# SCH_Flight-Computer-V4_2024-07-29.net
KiCad netlist of a schematic drawn in EasyEDA
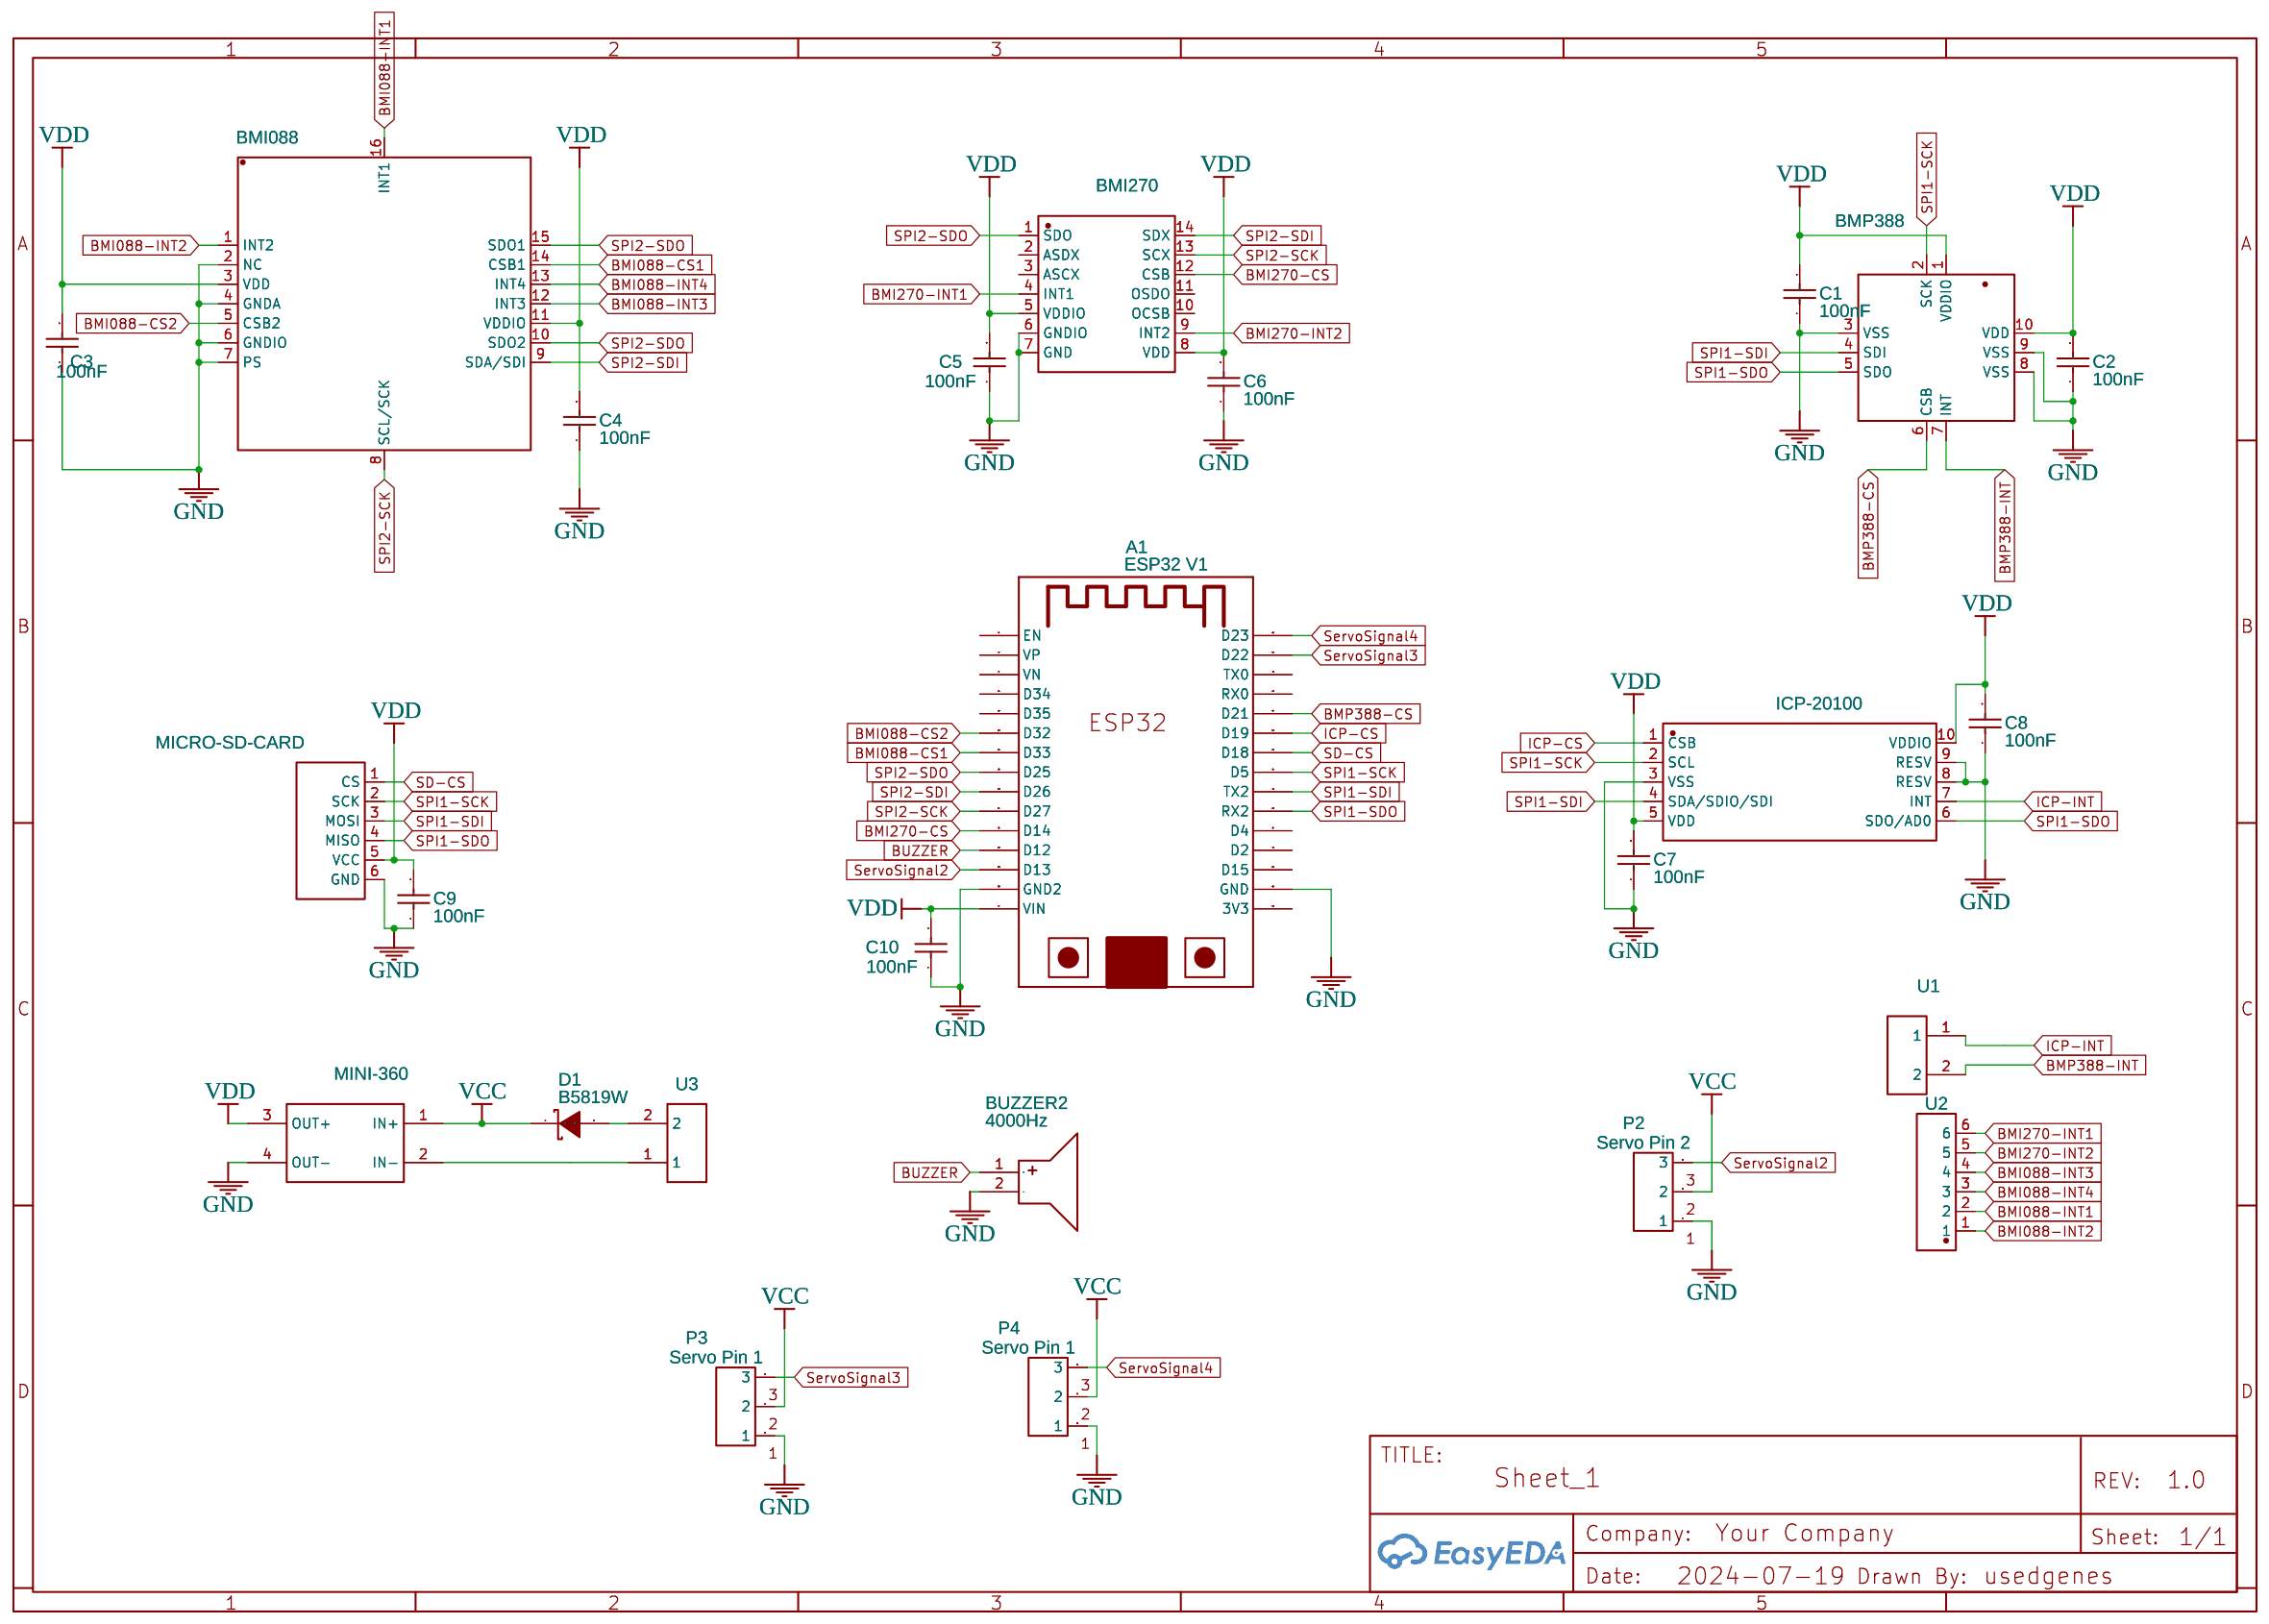
[diagram p0: schematic sheet]

(export (version "E")
  (design (tool "Eeschema 10.0.6"))
  (components
    (comp (ref "A1") (value "ESP32 V1") (libsource (lib "") (part "ESP32-DEVKIT-V1-30PIN")))
    (comp (ref "BMI088")
      (value "BMI088")
      (fields (field (name "Manufacturer") "Bosch(博世)"))
      (libsource (lib "") (part "BMI088"))
    )
    (comp (ref "BMI270")
      (value "BMI270")
      (fields (field (name "Manufacturer") "Bosch(博世)"))
      (libsource (lib "") (part "BMI270"))
    )
    (comp (ref "BMP388")
      (value "BMP388")
      (fields (field (name "Manufacturer") "Bosch(博世)"))
      (libsource (lib "") (part "BMP388"))
    )
    (comp (ref "BUZZER2")
      (value "4000Hz")
      (fields
        (field (name "Manufacturer Part") "SKY-1475-0540-45P7.6")
        (field (name "Manufacturer") "S&S(海旭)")
      )
      (libsource (lib "") (part "SKY-1475-0540-45P7.6"))
    )
    (comp (ref "C1")
      (value "100nF")
      (fields
        (field (name "Manufacturer Part") "CL05B104KO5NNNC")
        (field (name "Manufacturer") "SAMSUNG(三星)")
      )
      (libsource (lib "") (part "CL05B104KO5NNNC"))
    )
    (comp (ref "C2")
      (value "100nF")
      (fields
        (field (name "Manufacturer Part") "CL05B104KO5NNNC")
        (field (name "Manufacturer") "SAMSUNG(三星)")
      )
      (libsource (lib "") (part "CL05B104KO5NNNC"))
    )
    (comp (ref "C3")
      (value "100nF")
      (fields
        (field (name "Manufacturer Part") "CL05B104KO5NNNC")
        (field (name "Manufacturer") "SAMSUNG(三星)")
      )
      (libsource (lib "") (part "CL05B104KO5NNNC"))
    )
    (comp (ref "C4")
      (value "100nF")
      (fields
        (field (name "Manufacturer Part") "CL05B104KO5NNNC")
        (field (name "Manufacturer") "SAMSUNG(三星)")
      )
      (libsource (lib "") (part "CL05B104KO5NNNC"))
    )
    (comp (ref "C5")
      (value "100nF")
      (fields
        (field (name "Manufacturer Part") "CL05B104KO5NNNC")
        (field (name "Manufacturer") "SAMSUNG(三星)")
      )
      (libsource (lib "") (part "CL05B104KO5NNNC"))
    )
    (comp (ref "C6")
      (value "100nF")
      (fields
        (field (name "Manufacturer Part") "CL05B104KO5NNNC")
        (field (name "Manufacturer") "SAMSUNG(三星)")
      )
      (libsource (lib "") (part "CL05B104KO5NNNC"))
    )
    (comp (ref "C7")
      (value "100nF")
      (fields
        (field (name "Manufacturer Part") "CL05B104KO5NNNC")
        (field (name "Manufacturer") "SAMSUNG(三星)")
      )
      (libsource (lib "") (part "CL05B104KO5NNNC"))
    )
    (comp (ref "C8")
      (value "100nF")
      (fields
        (field (name "Manufacturer Part") "CL05B104KO5NNNC")
        (field (name "Manufacturer") "SAMSUNG(三星)")
      )
      (libsource (lib "") (part "CL05B104KO5NNNC"))
    )
    (comp (ref "C9")
      (value "100nF")
      (fields
        (field (name "Manufacturer Part") "CL05B104KO5NNNC")
        (field (name "Manufacturer") "SAMSUNG(三星)")
      )
      (libsource (lib "") (part "CL05B104KO5NNNC"))
    )
    (comp (ref "C10")
      (value "100nF")
      (fields
        (field (name "Manufacturer Part") "CL05B104KO5NNNC")
        (field (name "Manufacturer") "SAMSUNG(三星)")
      )
      (libsource (lib "") (part "CL05B104KO5NNNC"))
    )
    (comp (ref "D1")
      (value "B5819W")
      (fields (field (name "Manufacturer") "MDD(辰达半导体)"))
      (libsource (lib "") (part "B5819W"))
    )
    (comp (ref "ICP-20100")
      (value "ICP-20100")
      (fields (field (name "Manufacturer") "TDK"))
      (libsource (lib "") (part "ICP-20100"))
    )
    (comp (ref "MICRO-SD-CARD") (value "MicroSDCardAdapter") (libsource (lib "") (part "MicroSDCardAdapter")))
    (comp (ref "MINI-360") (value "MINI-360") (libsource (lib "") (part "MINI-360")))
    (comp (ref "P2")
      (value "Servo Pin 2")
      (fields
        (field (name "Manufacturer Part") "Female headerHDR1X8-2.54")
        (field (name "Manufacturer") "BOOMELE")
      )
      (libsource (lib "") (part "HEADER PAD 3X RMM COPY"))
    )
    (comp (ref "P3")
      (value "Servo Pin 1")
      (fields
        (field (name "Manufacturer Part") "Female headerHDR1X8-2.54")
        (field (name "Manufacturer") "BOOMELE")
      )
      (libsource (lib "") (part "HEADER PAD 3X RMM COPY"))
    )
    (comp (ref "P4")
      (value "Servo Pin 1")
      (fields
        (field (name "Manufacturer Part") "Female headerHDR1X8-2.54")
        (field (name "Manufacturer") "BOOMELE")
      )
      (libsource (lib "") (part "HEADER PAD 3X RMM COPY"))
    )
    (comp (ref "U1") (value "Power Pins") (libsource (lib "") (part "1X2_1")))
    (comp (ref "U2")
      (value "PIN HEADER 1X6PIN 2.54MM 6P OK COPY")
      (libsource (lib "") (part "PIN HEADER 1X6PIN 2.54MM 6P OK COPY"))
    )
    (comp (ref "U3") (value "Power Pins") (libsource (lib "") (part "1X2")))
  )
  (nets
    (net (code "1") (name "BMI088-CS1") (class "Default")
      (node (ref "A1") (pin "D33") (pinfunction "D33_D33") (pintype "unspecified"))
      (node (ref "BMI088") (pin "14") (pinfunction "CSB1_14") (pintype "unspecified"))
    )
    (net (code "2") (name "BMI088-CS2") (class "Default")
      (node (ref "A1") (pin "D32") (pinfunction "D32_D32") (pintype "unspecified"))
      (node (ref "BMI088") (pin "5") (pinfunction "CSB2_5") (pintype "unspecified"))
    )
    (net (code "3") (name "BMI088-INT1") (class "Default")
      (node (ref "BMI088") (pin "16") (pinfunction "INT1_16") (pintype "unspecified"))
      (node (ref "U2") (pin "2") (pinfunction "2_2") (pintype "unspecified"))
    )
    (net (code "4") (name "BMI088-INT2") (class "Default")
      (node (ref "BMI088") (pin "1") (pinfunction "INT2_1") (pintype "unspecified"))
      (node (ref "U2") (pin "1") (pinfunction "1_1") (pintype "unspecified"))
    )
    (net (code "5") (name "BMI088-INT3") (class "Default")
      (node (ref "BMI088") (pin "12") (pinfunction "INT3_12") (pintype "unspecified"))
      (node (ref "U2") (pin "4") (pinfunction "4_4") (pintype "unspecified"))
    )
    (net (code "6") (name "BMI088-INT4") (class "Default")
      (node (ref "BMI088") (pin "13") (pinfunction "INT4_13") (pintype "unspecified"))
      (node (ref "U2") (pin "3") (pinfunction "3_3") (pintype "unspecified"))
    )
    (net (code "7") (name "BMI270-CS") (class "Default")
      (node (ref "A1") (pin "D14") (pinfunction "D14_D14") (pintype "unspecified"))
      (node (ref "BMI270") (pin "12") (pinfunction "CSB_12") (pintype "unspecified"))
    )
    (net (code "8") (name "BMI270-INT1") (class "Default")
      (node (ref "BMI270") (pin "4") (pinfunction "INT1_4") (pintype "unspecified"))
      (node (ref "U2") (pin "6") (pinfunction "6_6") (pintype "unspecified"))
    )
    (net (code "9") (name "BMI270-INT2") (class "Default")
      (node (ref "BMI270") (pin "9") (pinfunction "INT2_9") (pintype "unspecified"))
      (node (ref "U2") (pin "5") (pinfunction "5_5") (pintype "unspecified"))
    )
    (net (code "10") (name "BMP388-CS") (class "Default")
      (node (ref "A1") (pin "D21") (pinfunction "D21_D21") (pintype "unspecified"))
      (node (ref "BMP388") (pin "6") (pinfunction "CSB_6") (pintype "unspecified"))
    )
    (net (code "11") (name "BMP388-INT") (class "Default")
      (node (ref "BMP388") (pin "7") (pinfunction "INT_7") (pintype "unspecified"))
      (node (ref "U1") (pin "2") (pinfunction "2_2") (pintype "unspecified"))
    )
    (net (code "12") (name "BUZZER") (class "Default")
      (node (ref "A1") (pin "D12") (pinfunction "D12_D12") (pintype "unspecified"))
      (node (ref "BUZZER2") (pin "1") (pinfunction "+_1") (pintype "unspecified"))
    )
    (net (code "13") (name "GND") (class "Default")
      (node (ref "A1") (pin "GND") (pinfunction "GND_GND") (pintype "unspecified"))
      (node (ref "A1") (pin "GND2") (pinfunction "GND2_GND2") (pintype "unspecified"))
      (node (ref "BMI088") (pin "2") (pinfunction "NC_2") (pintype "unspecified"))
      (node (ref "BMI088") (pin "4") (pinfunction "GNDA_4") (pintype "unspecified"))
      (node (ref "BMI088") (pin "6") (pinfunction "GNDIO_6") (pintype "unspecified"))
      (node (ref "BMI088") (pin "7") (pinfunction "PS_7") (pintype "unspecified"))
      (node (ref "BMI270") (pin "6") (pinfunction "GNDIO_6") (pintype "unspecified"))
      (node (ref "BMI270") (pin "7") (pinfunction "GND_7") (pintype "unspecified"))
      (node (ref "BMP388") (pin "3") (pinfunction "VSS_3") (pintype "unspecified"))
      (node (ref "BMP388") (pin "8") (pinfunction "VSS_8") (pintype "unspecified"))
      (node (ref "BMP388") (pin "9") (pinfunction "VSS_9") (pintype "unspecified"))
      (node (ref "BUZZER2") (pin "2") (pinfunction "-_2") (pintype "unspecified"))
      (node (ref "C1") (pin "1") (pinfunction "1_1") (pintype "input"))
      (node (ref "C10") (pin "1") (pinfunction "1_1") (pintype "input"))
      (node (ref "C2") (pin "1") (pinfunction "1_1") (pintype "input"))
      (node (ref "C3") (pin "1") (pinfunction "1_1") (pintype "input"))
      (node (ref "C4") (pin "1") (pinfunction "1_1") (pintype "input"))
      (node (ref "C5") (pin "1") (pinfunction "1_1") (pintype "input"))
      (node (ref "C6") (pin "1") (pinfunction "1_1") (pintype "input"))
      (node (ref "C7") (pin "1") (pinfunction "1_1") (pintype "input"))
      (node (ref "C8") (pin "1") (pinfunction "1_1") (pintype "input"))
      (node (ref "C9") (pin "1") (pinfunction "1_1") (pintype "input"))
      (node (ref "ICP-20100") (pin "3") (pinfunction "VSS_3") (pintype "unspecified"))
      (node (ref "ICP-20100") (pin "8") (pinfunction "RESV_8") (pintype "unspecified"))
      (node (ref "ICP-20100") (pin "9") (pinfunction "RESV_9") (pintype "unspecified"))
      (node (ref "MICRO-SD-CARD") (pin "6") (pinfunction "GND_6") (pintype "passive"))
      (node (ref "MINI-360") (pin "4") (pinfunction "OUT-_4") (pintype "unspecified"))
      (node (ref "P2") (pin "1") (pinfunction "1_1") (pintype "unspecified"))
      (node (ref "P3") (pin "1") (pinfunction "1_1") (pintype "unspecified"))
      (node (ref "P4") (pin "1") (pinfunction "1_1") (pintype "unspecified"))
    )
    (net (code "14") (name "ICP-CS") (class "Default")
      (node (ref "A1") (pin "D19") (pinfunction "D19_D19") (pintype "unspecified"))
      (node (ref "ICP-20100") (pin "1") (pinfunction "CSB_1") (pintype "unspecified"))
    )
    (net (code "15") (name "ICP-INT") (class "Default")
      (node (ref "ICP-20100") (pin "7") (pinfunction "INT_7") (pintype "unspecified"))
      (node (ref "U1") (pin "1") (pinfunction "1_1") (pintype "unspecified"))
    )
    (net (code "16") (name "Net-(D1-A)") (class "Default")
      (node (ref "D1") (pin "2") (pinfunction "A_2") (pintype "unspecified"))
      (node (ref "U3") (pin "2") (pinfunction "2_2") (pintype "unspecified"))
    )
    (net (code "17") (name "Net-(MINI-360-IN-)") (class "Default")
      (node (ref "MINI-360") (pin "2") (pinfunction "IN-_2") (pintype "unspecified"))
      (node (ref "U3") (pin "1") (pinfunction "1_1") (pintype "unspecified"))
    )
    (net (code "18") (name "SD-CS") (class "Default")
      (node (ref "A1") (pin "D18") (pinfunction "D18_D18") (pintype "unspecified"))
      (node (ref "MICRO-SD-CARD") (pin "1") (pinfunction "CS_1") (pintype "bidirectional"))
    )
    (net (code "19") (name "SPI1-SCK") (class "Default")
      (node (ref "A1") (pin "D5") (pinfunction "D5_D5") (pintype "unspecified"))
      (node (ref "BMP388") (pin "2") (pinfunction "SCK_2") (pintype "unspecified"))
      (node (ref "ICP-20100") (pin "2") (pinfunction "SCL_2") (pintype "unspecified"))
      (node (ref "MICRO-SD-CARD") (pin "2") (pinfunction "SCK_2") (pintype "bidirectional"))
    )
    (net (code "20") (name "SPI1-SDI") (class "Default")
      (node (ref "A1") (pin "TX2") (pinfunction "TX2_TX2") (pintype "unspecified"))
      (node (ref "BMP388") (pin "4") (pinfunction "SDI_4") (pintype "unspecified"))
      (node (ref "ICP-20100") (pin "4") (pinfunction "SDA/SDIO/SDI_4") (pintype "unspecified"))
      (node (ref "MICRO-SD-CARD") (pin "3") (pinfunction "MOSI_3") (pintype "passive"))
    )
    (net (code "21") (name "SPI1-SDO") (class "Default")
      (node (ref "A1") (pin "RX2") (pinfunction "RX2_RX2") (pintype "unspecified"))
      (node (ref "BMP388") (pin "5") (pinfunction "SDO_5") (pintype "unspecified"))
      (node (ref "ICP-20100") (pin "6") (pinfunction "SDO/AD0_6") (pintype "unspecified"))
      (node (ref "MICRO-SD-CARD") (pin "4") (pinfunction "MISO_4") (pintype "bidirectional"))
    )
    (net (code "22") (name "SPI2-SCK") (class "Default")
      (node (ref "A1") (pin "D27") (pinfunction "D27_D27") (pintype "unspecified"))
      (node (ref "BMI088") (pin "8") (pinfunction "SCL/SCK_8") (pintype "unspecified"))
      (node (ref "BMI270") (pin "13") (pinfunction "SCX_13") (pintype "unspecified"))
    )
    (net (code "23") (name "SPI2-SDI") (class "Default")
      (node (ref "A1") (pin "D26") (pinfunction "D26_D26") (pintype "unspecified"))
      (node (ref "BMI088") (pin "9") (pinfunction "SDA/SDI_9") (pintype "unspecified"))
      (node (ref "BMI270") (pin "14") (pinfunction "SDX_14") (pintype "unspecified"))
    )
    (net (code "24") (name "SPI2-SDO") (class "Default")
      (node (ref "A1") (pin "D25") (pinfunction "D25_D25") (pintype "unspecified"))
      (node (ref "BMI088") (pin "10") (pinfunction "SDO2_10") (pintype "unspecified"))
      (node (ref "BMI088") (pin "15") (pinfunction "SDO1_15") (pintype "unspecified"))
      (node (ref "BMI270") (pin "1") (pinfunction "SDO_1") (pintype "unspecified"))
    )
    (net (code "25") (name "ServoSignal2") (class "Default")
      (node (ref "A1") (pin "D13") (pinfunction "D13_D13") (pintype "unspecified"))
      (node (ref "P2") (pin "3") (pinfunction "3_3") (pintype "unspecified"))
    )
    (net (code "26") (name "ServoSignal3") (class "Default")
      (node (ref "A1") (pin "D22") (pinfunction "D22_D22") (pintype "unspecified"))
      (node (ref "P3") (pin "3") (pinfunction "3_3") (pintype "unspecified"))
    )
    (net (code "27") (name "ServoSignal4") (class "Default")
      (node (ref "A1") (pin "D23") (pinfunction "D23_D23") (pintype "unspecified"))
      (node (ref "P4") (pin "3") (pinfunction "3_3") (pintype "unspecified"))
    )
    (net (code "28") (name "VCC") (class "Default")
      (node (ref "D1") (pin "1") (pinfunction "K_1") (pintype "unspecified"))
      (node (ref "MINI-360") (pin "1") (pinfunction "IN+_1") (pintype "unspecified"))
      (node (ref "P2") (pin "2") (pinfunction "2_2") (pintype "unspecified"))
      (node (ref "P3") (pin "2") (pinfunction "2_2") (pintype "unspecified"))
      (node (ref "P4") (pin "2") (pinfunction "2_2") (pintype "unspecified"))
    )
    (net (code "29") (name "VDD") (class "Default")
      (node (ref "A1") (pin "VIN") (pinfunction "VIN_VIN") (pintype "unspecified"))
      (node (ref "BMI088") (pin "11") (pinfunction "VDDIO_11") (pintype "unspecified"))
      (node (ref "BMI088") (pin "3") (pinfunction "VDD_3") (pintype "unspecified"))
      (node (ref "BMI270") (pin "5") (pinfunction "VDDIO_5") (pintype "unspecified"))
      (node (ref "BMI270") (pin "8") (pinfunction "VDD_8") (pintype "unspecified"))
      (node (ref "BMP388") (pin "1") (pinfunction "VDDIO_1") (pintype "unspecified"))
      (node (ref "BMP388") (pin "10") (pinfunction "VDD_10") (pintype "unspecified"))
      (node (ref "C1") (pin "2") (pinfunction "2_2") (pintype "input"))
      (node (ref "C10") (pin "2") (pinfunction "2_2") (pintype "input"))
      (node (ref "C2") (pin "2") (pinfunction "2_2") (pintype "input"))
      (node (ref "C3") (pin "2") (pinfunction "2_2") (pintype "input"))
      (node (ref "C4") (pin "2") (pinfunction "2_2") (pintype "input"))
      (node (ref "C5") (pin "2") (pinfunction "2_2") (pintype "input"))
      (node (ref "C6") (pin "2") (pinfunction "2_2") (pintype "input"))
      (node (ref "C7") (pin "2") (pinfunction "2_2") (pintype "input"))
      (node (ref "C8") (pin "2") (pinfunction "2_2") (pintype "input"))
      (node (ref "C9") (pin "2") (pinfunction "2_2") (pintype "input"))
      (node (ref "ICP-20100") (pin "10") (pinfunction "VDDIO_10") (pintype "unspecified"))
      (node (ref "ICP-20100") (pin "5") (pinfunction "VDD_5") (pintype "unspecified"))
      (node (ref "MICRO-SD-CARD") (pin "5") (pinfunction "VCC_5") (pintype "passive"))
      (node (ref "MINI-360") (pin "3") (pinfunction "OUT+_3") (pintype "unspecified"))
    )
    (net (code "30") (name "unconnected-(A1-Pad3V3)") (class "Default")
      (node (ref "A1") (pin "3V3") (pinfunction "3V3_3V3") (pintype "unspecified"))
    )
    (net (code "31") (name "unconnected-(A1-PadD2)") (class "Default")
      (node (ref "A1") (pin "D2") (pinfunction "D2_D2") (pintype "unspecified"))
    )
    (net (code "32") (name "unconnected-(A1-PadD4)") (class "Default")
      (node (ref "A1") (pin "D4") (pinfunction "D4_D4") (pintype "unspecified"))
    )
    (net (code "33") (name "unconnected-(A1-PadD15)") (class "Default")
      (node (ref "A1") (pin "D15") (pinfunction "D15_D15") (pintype "unspecified"))
    )
    (net (code "34") (name "unconnected-(A1-PadD34)") (class "Default")
      (node (ref "A1") (pin "D34") (pinfunction "D34_D34") (pintype "unspecified"))
    )
    (net (code "35") (name "unconnected-(A1-PadD35)") (class "Default")
      (node (ref "A1") (pin "D35") (pinfunction "D35_D35") (pintype "unspecified"))
    )
    (net (code "36") (name "unconnected-(A1-PadEN)") (class "Default")
      (node (ref "A1") (pin "EN") (pinfunction "EN_EN") (pintype "unspecified"))
    )
    (net (code "37") (name "unconnected-(A1-PadRX0)") (class "Default")
      (node (ref "A1") (pin "RX0") (pinfunction "RX0_RX0") (pintype "unspecified"))
    )
    (net (code "38") (name "unconnected-(A1-PadTX0)") (class "Default")
      (node (ref "A1") (pin "TX0") (pinfunction "TX0_TX0") (pintype "unspecified"))
    )
    (net (code "39") (name "unconnected-(A1-PadVN)") (class "Default")
      (node (ref "A1") (pin "VN") (pinfunction "VN_VN") (pintype "unspecified"))
    )
    (net (code "40") (name "unconnected-(A1-PadVP)") (class "Default")
      (node (ref "A1") (pin "VP") (pinfunction "VP_VP") (pintype "unspecified"))
    )
    (net (code "41") (name "unconnected-(BMI270-ASCX-Pad3)") (class "Default")
      (node (ref "BMI270") (pin "3") (pinfunction "ASCX_3") (pintype "unspecified"))
    )
    (net (code "42") (name "unconnected-(BMI270-ASDX-Pad2)") (class "Default")
      (node (ref "BMI270") (pin "2") (pinfunction "ASDX_2") (pintype "unspecified"))
    )
    (net (code "43") (name "unconnected-(BMI270-OCSB-Pad10)") (class "Default")
      (node (ref "BMI270") (pin "10") (pinfunction "OCSB_10") (pintype "unspecified"))
    )
    (net (code "44") (name "unconnected-(BMI270-OSDO-Pad11)") (class "Default")
      (node (ref "BMI270") (pin "11") (pinfunction "OSDO_11") (pintype "unspecified"))
    )
  )
)
